# StraightThumbs.net
KiCad netlist of a schematic drawn in EAGLE
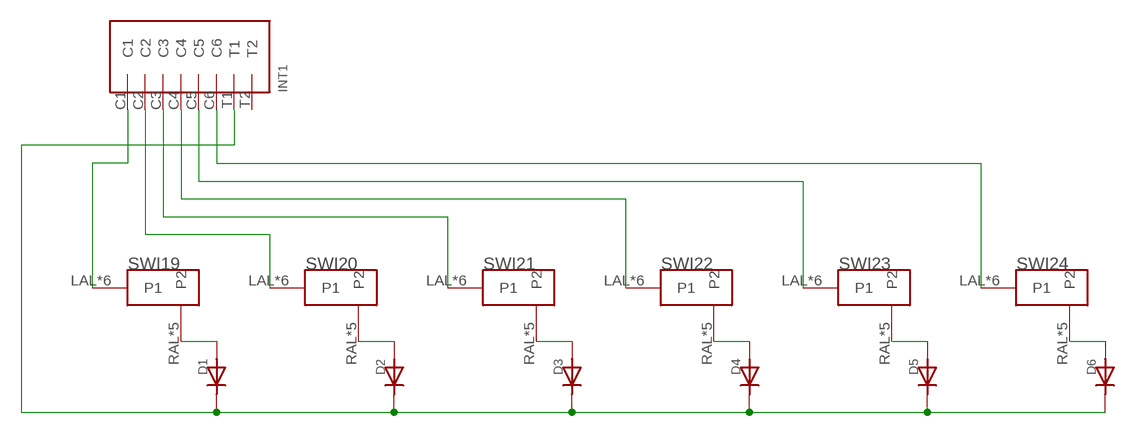
[diagram p0: schematic, sheet 1]

(export (version "E")
  (design (tool "Eeschema 10.0.6"))
  (components
    (comp (ref "D1")
      (value "DIODE")
      (footprint "eagle-import:DIODE_COMBO")
      (libsource (lib "eagle-import") (part "DIODE"))
    )
    (comp (ref "D2")
      (value "DIODE")
      (footprint "eagle-import:DIODE_COMBO")
      (libsource (lib "eagle-import") (part "DIODE"))
    )
    (comp (ref "D3")
      (value "DIODE")
      (footprint "eagle-import:DIODE_COMBO")
      (libsource (lib "eagle-import") (part "DIODE"))
    )
    (comp (ref "D4")
      (value "DIODE")
      (footprint "eagle-import:DIODE_COMBO")
      (libsource (lib "eagle-import") (part "DIODE"))
    )
    (comp (ref "D5")
      (value "DIODE")
      (footprint "eagle-import:DIODE_COMBO")
      (libsource (lib "eagle-import") (part "DIODE"))
    )
    (comp (ref "D6")
      (value "DIODE")
      (footprint "eagle-import:DIODE_COMBO")
      (libsource (lib "eagle-import") (part "DIODE"))
    )
    (comp (ref "INT1")
      (value "INTRCNNT4X2")
      (footprint "eagle-import:INTRRIBBON")
      (libsource (lib "eagle-import") (part "INTRCNNT4X2"))
    )
    (comp (ref "SWI19")
      (value "MX/ALPSDOUBLESIDED")
      (footprint "eagle-import:DOUBLED_MX_ALPS")
      (libsource (lib "eagle-import") (part "MX/ALPSDOUBLESIDED"))
    )
    (comp (ref "SWI20")
      (value "MX/ALPSDOUBLESIDED")
      (footprint "eagle-import:DOUBLED_MX_ALPS")
      (libsource (lib "eagle-import") (part "MX/ALPSDOUBLESIDED"))
    )
    (comp (ref "SWI21")
      (value "MX/ALPSDOUBLESIDED")
      (footprint "eagle-import:DOUBLED_MX_ALPS")
      (libsource (lib "eagle-import") (part "MX/ALPSDOUBLESIDED"))
    )
    (comp (ref "SWI22")
      (value "MX/ALPSDOUBLESIDED")
      (footprint "eagle-import:DOUBLED_MX_ALPS")
      (libsource (lib "eagle-import") (part "MX/ALPSDOUBLESIDED"))
    )
    (comp (ref "SWI23")
      (value "MX/ALPSDOUBLESIDED")
      (footprint "eagle-import:DOUBLED_MX_ALPS")
      (libsource (lib "eagle-import") (part "MX/ALPSDOUBLESIDED"))
    )
    (comp (ref "SWI24")
      (value "MX/ALPSDOUBLESIDED")
      (footprint "eagle-import:DOUBLED_MX_ALPS")
      (libsource (lib "eagle-import") (part "MX/ALPSDOUBLESIDED"))
    )
  )
  (nets
    (net (code "1") (name "Net-(D1-AN-PadANOSB)") (class "Default")
      (node (ref "D1") (pin "ANOSB") (pinfunction "AN_ANOSB") (pintype "bidirectional"))
      (node (ref "D1") (pin "ANOST") (pinfunction "AN_ANOST") (pintype "bidirectional"))
      (node (ref "D1") (pin "ANOT") (pinfunction "AN_ANOT") (pintype "bidirectional"))
      (node (ref "SWI19") (pin "RAL") (pinfunction "P2_RAL") (pintype "bidirectional"))
      (node (ref "SWI19") (pin "RAR") (pinfunction "P2_RAR") (pintype "bidirectional"))
      (node (ref "SWI19") (pin "RCL") (pinfunction "P2_RCL") (pintype "bidirectional"))
      (node (ref "SWI19") (pin "RCR") (pinfunction "P2_RCR") (pintype "bidirectional"))
      (node (ref "SWI19") (pin "RLMID") (pinfunction "P2_RLMID") (pintype "bidirectional"))
    )
    (net (code "2") (name "Net-(D1-CAT-PadCATSB)") (class "Default")
      (node (ref "D1") (pin "CATSB") (pinfunction "CAT_CATSB") (pintype "bidirectional"))
      (node (ref "D1") (pin "CATST") (pinfunction "CAT_CATST") (pintype "bidirectional"))
      (node (ref "D1") (pin "CATT") (pinfunction "CAT_CATT") (pintype "bidirectional"))
      (node (ref "D2") (pin "CATSB") (pinfunction "CAT_CATSB") (pintype "bidirectional"))
      (node (ref "D2") (pin "CATST") (pinfunction "CAT_CATST") (pintype "bidirectional"))
      (node (ref "D2") (pin "CATT") (pinfunction "CAT_CATT") (pintype "bidirectional"))
      (node (ref "D3") (pin "CATSB") (pinfunction "CAT_CATSB") (pintype "bidirectional"))
      (node (ref "D3") (pin "CATST") (pinfunction "CAT_CATST") (pintype "bidirectional"))
      (node (ref "D3") (pin "CATT") (pinfunction "CAT_CATT") (pintype "bidirectional"))
      (node (ref "D4") (pin "CATSB") (pinfunction "CAT_CATSB") (pintype "bidirectional"))
      (node (ref "D4") (pin "CATST") (pinfunction "CAT_CATST") (pintype "bidirectional"))
      (node (ref "D4") (pin "CATT") (pinfunction "CAT_CATT") (pintype "bidirectional"))
      (node (ref "D5") (pin "CATSB") (pinfunction "CAT_CATSB") (pintype "bidirectional"))
      (node (ref "D5") (pin "CATST") (pinfunction "CAT_CATST") (pintype "bidirectional"))
      (node (ref "D5") (pin "CATT") (pinfunction "CAT_CATT") (pintype "bidirectional"))
      (node (ref "D6") (pin "CATSB") (pinfunction "CAT_CATSB") (pintype "bidirectional"))
      (node (ref "D6") (pin "CATST") (pinfunction "CAT_CATST") (pintype "bidirectional"))
      (node (ref "D6") (pin "CATT") (pinfunction "CAT_CATT") (pintype "bidirectional"))
      (node (ref "INT1") (pin "T1") (pinfunction "T1_T1") (pintype "bidirectional"))
    )
    (net (code "3") (name "Net-(D2-AN-PadANOSB)") (class "Default")
      (node (ref "D2") (pin "ANOSB") (pinfunction "AN_ANOSB") (pintype "bidirectional"))
      (node (ref "D2") (pin "ANOST") (pinfunction "AN_ANOST") (pintype "bidirectional"))
      (node (ref "D2") (pin "ANOT") (pinfunction "AN_ANOT") (pintype "bidirectional"))
      (node (ref "SWI20") (pin "RAL") (pinfunction "P2_RAL") (pintype "bidirectional"))
      (node (ref "SWI20") (pin "RAR") (pinfunction "P2_RAR") (pintype "bidirectional"))
      (node (ref "SWI20") (pin "RCL") (pinfunction "P2_RCL") (pintype "bidirectional"))
      (node (ref "SWI20") (pin "RCR") (pinfunction "P2_RCR") (pintype "bidirectional"))
      (node (ref "SWI20") (pin "RLMID") (pinfunction "P2_RLMID") (pintype "bidirectional"))
    )
    (net (code "4") (name "Net-(D3-AN-PadANOSB)") (class "Default")
      (node (ref "D3") (pin "ANOSB") (pinfunction "AN_ANOSB") (pintype "bidirectional"))
      (node (ref "D3") (pin "ANOST") (pinfunction "AN_ANOST") (pintype "bidirectional"))
      (node (ref "D3") (pin "ANOT") (pinfunction "AN_ANOT") (pintype "bidirectional"))
      (node (ref "SWI21") (pin "RAL") (pinfunction "P2_RAL") (pintype "bidirectional"))
      (node (ref "SWI21") (pin "RAR") (pinfunction "P2_RAR") (pintype "bidirectional"))
      (node (ref "SWI21") (pin "RCL") (pinfunction "P2_RCL") (pintype "bidirectional"))
      (node (ref "SWI21") (pin "RCR") (pinfunction "P2_RCR") (pintype "bidirectional"))
      (node (ref "SWI21") (pin "RLMID") (pinfunction "P2_RLMID") (pintype "bidirectional"))
    )
    (net (code "5") (name "Net-(D4-AN-PadANOSB)") (class "Default")
      (node (ref "D4") (pin "ANOSB") (pinfunction "AN_ANOSB") (pintype "bidirectional"))
      (node (ref "D4") (pin "ANOST") (pinfunction "AN_ANOST") (pintype "bidirectional"))
      (node (ref "D4") (pin "ANOT") (pinfunction "AN_ANOT") (pintype "bidirectional"))
      (node (ref "SWI22") (pin "RAL") (pinfunction "P2_RAL") (pintype "bidirectional"))
      (node (ref "SWI22") (pin "RAR") (pinfunction "P2_RAR") (pintype "bidirectional"))
      (node (ref "SWI22") (pin "RCL") (pinfunction "P2_RCL") (pintype "bidirectional"))
      (node (ref "SWI22") (pin "RCR") (pinfunction "P2_RCR") (pintype "bidirectional"))
      (node (ref "SWI22") (pin "RLMID") (pinfunction "P2_RLMID") (pintype "bidirectional"))
    )
    (net (code "6") (name "Net-(D5-AN-PadANOSB)") (class "Default")
      (node (ref "D5") (pin "ANOSB") (pinfunction "AN_ANOSB") (pintype "bidirectional"))
      (node (ref "D5") (pin "ANOST") (pinfunction "AN_ANOST") (pintype "bidirectional"))
      (node (ref "D5") (pin "ANOT") (pinfunction "AN_ANOT") (pintype "bidirectional"))
      (node (ref "SWI23") (pin "RAL") (pinfunction "P2_RAL") (pintype "bidirectional"))
      (node (ref "SWI23") (pin "RAR") (pinfunction "P2_RAR") (pintype "bidirectional"))
      (node (ref "SWI23") (pin "RCL") (pinfunction "P2_RCL") (pintype "bidirectional"))
      (node (ref "SWI23") (pin "RCR") (pinfunction "P2_RCR") (pintype "bidirectional"))
      (node (ref "SWI23") (pin "RLMID") (pinfunction "P2_RLMID") (pintype "bidirectional"))
    )
    (net (code "7") (name "Net-(D6-AN-PadANOSB)") (class "Default")
      (node (ref "D6") (pin "ANOSB") (pinfunction "AN_ANOSB") (pintype "bidirectional"))
      (node (ref "D6") (pin "ANOST") (pinfunction "AN_ANOST") (pintype "bidirectional"))
      (node (ref "D6") (pin "ANOT") (pinfunction "AN_ANOT") (pintype "bidirectional"))
      (node (ref "SWI24") (pin "RAL") (pinfunction "P2_RAL") (pintype "bidirectional"))
      (node (ref "SWI24") (pin "RAR") (pinfunction "P2_RAR") (pintype "bidirectional"))
      (node (ref "SWI24") (pin "RCL") (pinfunction "P2_RCL") (pintype "bidirectional"))
      (node (ref "SWI24") (pin "RCR") (pinfunction "P2_RCR") (pintype "bidirectional"))
      (node (ref "SWI24") (pin "RLMID") (pinfunction "P2_RLMID") (pintype "bidirectional"))
    )
    (net (code "8") (name "Net-(INT1-PadC1)") (class "Default")
      (node (ref "INT1") (pin "C1") (pinfunction "C1_C1") (pintype "bidirectional"))
      (node (ref "SWI19") (pin "LAL") (pinfunction "P1_LAL") (pintype "bidirectional"))
      (node (ref "SWI19") (pin "LAR") (pinfunction "P1_LAR") (pintype "bidirectional"))
      (node (ref "SWI19") (pin "LCL") (pinfunction "P1_LCL") (pintype "bidirectional"))
      (node (ref "SWI19") (pin "LCR") (pinfunction "P1_LCR") (pintype "bidirectional"))
      (node (ref "SWI19") (pin "LLP") (pinfunction "P1_LLP") (pintype "bidirectional"))
      (node (ref "SWI19") (pin "LRLP") (pinfunction "P1_LRLP") (pintype "bidirectional"))
    )
    (net (code "9") (name "Net-(INT1-PadC2)") (class "Default")
      (node (ref "INT1") (pin "C2") (pinfunction "C2_C2") (pintype "bidirectional"))
      (node (ref "SWI20") (pin "LAL") (pinfunction "P1_LAL") (pintype "bidirectional"))
      (node (ref "SWI20") (pin "LAR") (pinfunction "P1_LAR") (pintype "bidirectional"))
      (node (ref "SWI20") (pin "LCL") (pinfunction "P1_LCL") (pintype "bidirectional"))
      (node (ref "SWI20") (pin "LCR") (pinfunction "P1_LCR") (pintype "bidirectional"))
      (node (ref "SWI20") (pin "LLP") (pinfunction "P1_LLP") (pintype "bidirectional"))
      (node (ref "SWI20") (pin "LRLP") (pinfunction "P1_LRLP") (pintype "bidirectional"))
    )
    (net (code "10") (name "Net-(INT1-PadC3)") (class "Default")
      (node (ref "INT1") (pin "C3") (pinfunction "C3_C3") (pintype "bidirectional"))
      (node (ref "SWI21") (pin "LAL") (pinfunction "P1_LAL") (pintype "bidirectional"))
      (node (ref "SWI21") (pin "LAR") (pinfunction "P1_LAR") (pintype "bidirectional"))
      (node (ref "SWI21") (pin "LCL") (pinfunction "P1_LCL") (pintype "bidirectional"))
      (node (ref "SWI21") (pin "LCR") (pinfunction "P1_LCR") (pintype "bidirectional"))
      (node (ref "SWI21") (pin "LLP") (pinfunction "P1_LLP") (pintype "bidirectional"))
      (node (ref "SWI21") (pin "LRLP") (pinfunction "P1_LRLP") (pintype "bidirectional"))
    )
    (net (code "11") (name "Net-(INT1-PadC4)") (class "Default")
      (node (ref "INT1") (pin "C4") (pinfunction "C4_C4") (pintype "bidirectional"))
      (node (ref "SWI22") (pin "LAL") (pinfunction "P1_LAL") (pintype "bidirectional"))
      (node (ref "SWI22") (pin "LAR") (pinfunction "P1_LAR") (pintype "bidirectional"))
      (node (ref "SWI22") (pin "LCL") (pinfunction "P1_LCL") (pintype "bidirectional"))
      (node (ref "SWI22") (pin "LCR") (pinfunction "P1_LCR") (pintype "bidirectional"))
      (node (ref "SWI22") (pin "LLP") (pinfunction "P1_LLP") (pintype "bidirectional"))
      (node (ref "SWI22") (pin "LRLP") (pinfunction "P1_LRLP") (pintype "bidirectional"))
    )
    (net (code "12") (name "Net-(INT1-PadC5)") (class "Default")
      (node (ref "INT1") (pin "C5") (pinfunction "C5_C5") (pintype "bidirectional"))
      (node (ref "SWI23") (pin "LAL") (pinfunction "P1_LAL") (pintype "bidirectional"))
      (node (ref "SWI23") (pin "LAR") (pinfunction "P1_LAR") (pintype "bidirectional"))
      (node (ref "SWI23") (pin "LCL") (pinfunction "P1_LCL") (pintype "bidirectional"))
      (node (ref "SWI23") (pin "LCR") (pinfunction "P1_LCR") (pintype "bidirectional"))
      (node (ref "SWI23") (pin "LLP") (pinfunction "P1_LLP") (pintype "bidirectional"))
      (node (ref "SWI23") (pin "LRLP") (pinfunction "P1_LRLP") (pintype "bidirectional"))
    )
    (net (code "13") (name "Net-(INT1-PadC6)") (class "Default")
      (node (ref "INT1") (pin "C6") (pinfunction "C6_C6") (pintype "bidirectional"))
      (node (ref "SWI24") (pin "LAL") (pinfunction "P1_LAL") (pintype "bidirectional"))
      (node (ref "SWI24") (pin "LAR") (pinfunction "P1_LAR") (pintype "bidirectional"))
      (node (ref "SWI24") (pin "LCL") (pinfunction "P1_LCL") (pintype "bidirectional"))
      (node (ref "SWI24") (pin "LCR") (pinfunction "P1_LCR") (pintype "bidirectional"))
      (node (ref "SWI24") (pin "LLP") (pinfunction "P1_LLP") (pintype "bidirectional"))
      (node (ref "SWI24") (pin "LRLP") (pinfunction "P1_LRLP") (pintype "bidirectional"))
    )
    (net (code "14") (name "unconnected-(INT1-PadT2)") (class "Default")
      (node (ref "INT1") (pin "T2") (pinfunction "T2_T2") (pintype "bidirectional"))
    )
  )
)
